# MFX.net
KiCad netlist of a schematic drawn in Altium Designer
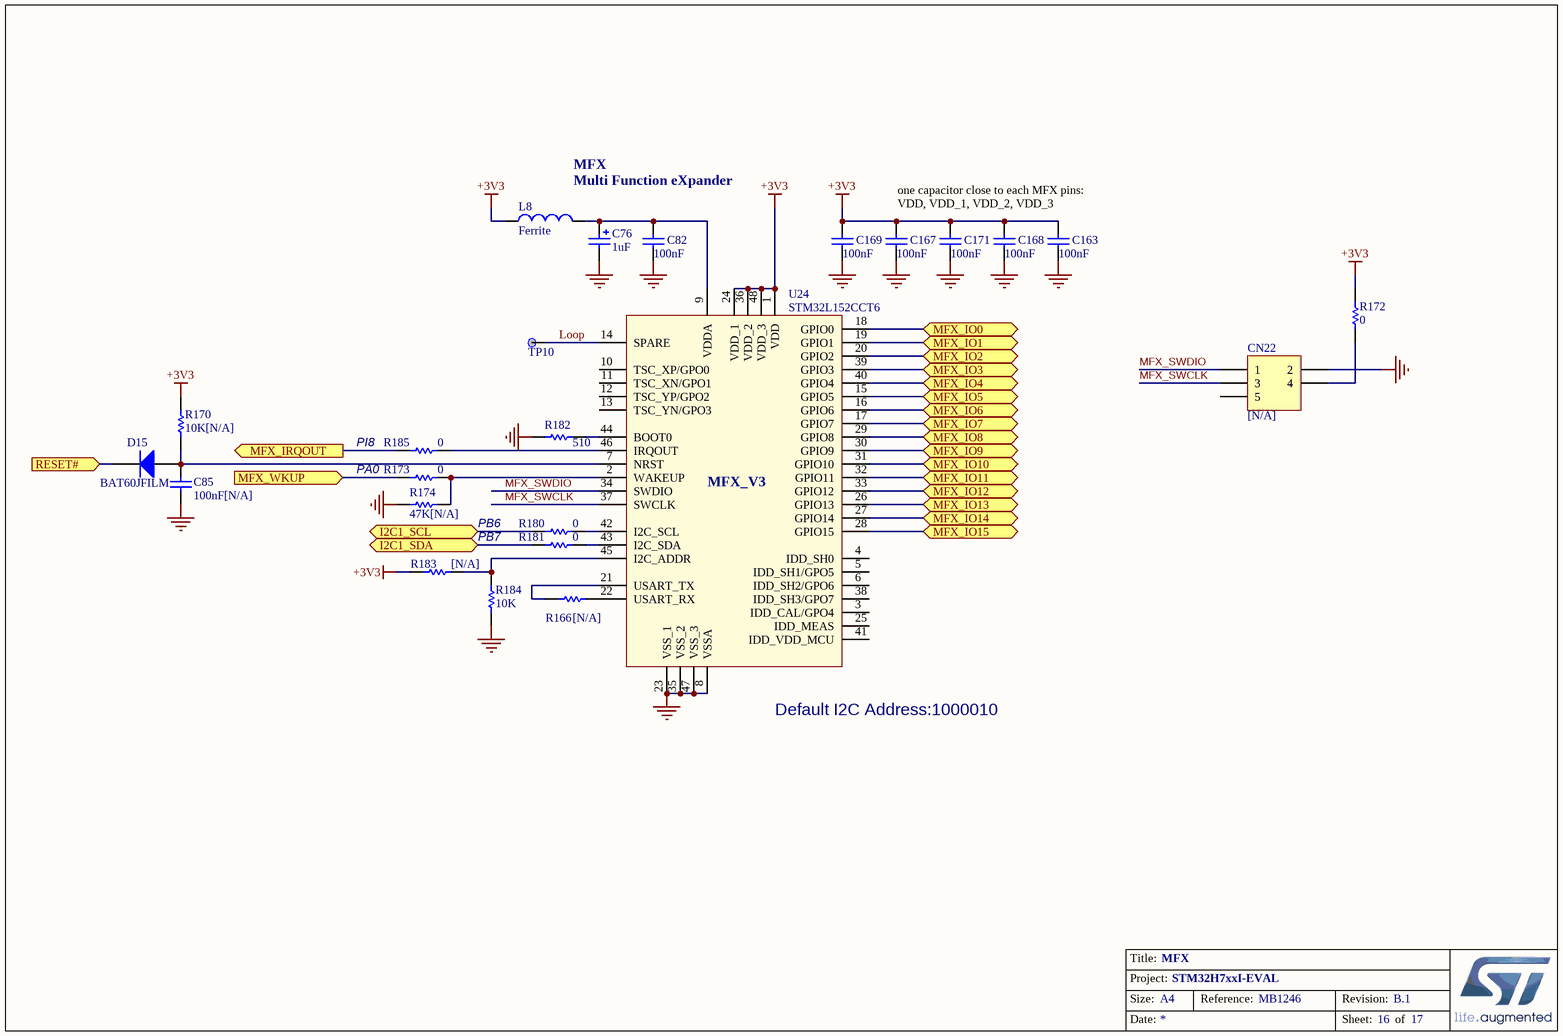
[diagram p0: MFX.SchDoc]

(export (version "E")
  (design (tool "Eeschema 10.0.6"))
  (components
    (comp (ref "C76")
      (value "1uF")
      (footprint "TAN-A")
      (description "Polarized Capacitor,1uF,16V,10%,typeA,AVX")
      (libsource (lib "MCD_TOOLS") (part "Cap_1uF_POL_10%_TANA"))
    )
    (comp (ref "C82")
      (value "100nF")
      (footprint "0402C")
      (description "Capacitor,100nF,16V,X7R,10%,0402,YAGEO")
      (libsource (lib "MCD_TOOLS") (part "Cap_100nF_X7R_10%_0402"))
    )
    (comp (ref "C85")
      (value "100nF[N/A]")
      (footprint "0402C")
      (description "Capacitor,100nF,16V,X7R,10%,0402,YAGEO")
      (libsource (lib "MCD_TOOLS") (part "Cap_100nF_X7R_10%_0402"))
    )
    (comp (ref "C163")
      (value "100nF")
      (footprint "0402C")
      (description "Capacitor,100nF,16V,X7R,10%,0402,YAGEO")
      (libsource (lib "MCD_TOOLS") (part "Cap_100nF_X7R_10%_0402"))
    )
    (comp (ref "C167")
      (value "100nF")
      (footprint "0402C")
      (description "Capacitor,100nF,16V,X7R,10%,0402,YAGEO")
      (libsource (lib "MCD_TOOLS") (part "Cap_100nF_X7R_10%_0402"))
    )
    (comp (ref "C168")
      (value "100nF")
      (footprint "0402C")
      (description "Capacitor,100nF,16V,X7R,10%,0402,YAGEO")
      (libsource (lib "MCD_TOOLS") (part "Cap_100nF_X7R_10%_0402"))
    )
    (comp (ref "C169")
      (value "100nF")
      (footprint "0402C")
      (description "Capacitor,100nF,16V,X7R,10%,0402,YAGEO")
      (libsource (lib "MCD_TOOLS") (part "Cap_100nF_X7R_10%_0402"))
    )
    (comp (ref "C171")
      (value "100nF")
      (footprint "0402C")
      (description "Capacitor,100nF,16V,X7R,10%,0402,YAGEO")
      (libsource (lib "MCD_TOOLS") (part "Cap_100nF_X7R_10%_0402"))
    )
    (comp (ref "CN22")
      (value "[N/A]")
      (footprint "HDR_2X3-1_2R54-6")
      (description "Header, 3-Pin, Dual row")
      (fields (field (name "PUBLISHER") "Altium Limited"))
      (libsource (lib "Miscellaneous Connectors") (part "Header 3X2"))
    )
    (comp (ref "D15")
      (value "BAT60JFILM")
      (footprint "SOD-323")
      (description "Default Diode")
      (fields (field (name "PUBLISHER") "Altium Limited"))
      (libsource (lib "Miscellaneous Devices") (part "Diode"))
    )
    (comp (ref "L8")
      (value "Ferrite")
      (footprint "0603L")
      (description "Bead,600R,350mA,0603,FCM1608KF-601T03,Tai-tech")
      (libsource (lib "MCD_TOOLS") (part "BEAD_600R_350MA_0603"))
    )
    (comp (ref "R166")
      (value "[N/A]")
      (footprint "0603R")
      (description "Resistor")
      (fields (field (name "PUBLISHER") "Altium Limited"))
      (libsource (lib "Miscellaneous Devices") (part "res1"))
    )
    (comp (ref "R170")
      (value "10K[N/A]")
      (footprint "0402R")
      (description "Resistor 0402 or 0603 or 0805")
      (libsource (lib "MCD_TOOLS") (part "Resistor_ST"))
    )
    (comp (ref "R172")
      (value "0")
      (footprint "0603R")
      (description "Resistor")
      (fields (field (name "PUBLISHER") "Altium Limited"))
      (libsource (lib "Miscellaneous Devices") (part "Res1"))
    )
    (comp (ref "R173")
      (value "0")
      (footprint "0603R")
      (description "Resistor")
      (fields (field (name "PUBLISHER") "Altium Limited"))
      (libsource (lib "Miscellaneous Devices") (part "Res1"))
    )
    (comp (ref "R174")
      (value "47K[N/A]")
      (footprint "0402R")
      (description "Resistor 0402 or 0603 or 0805")
      (libsource (lib "MCD_TOOLS") (part "Resistor_ST"))
    )
    (comp (ref "R180")
      (value "0")
      (footprint "0603R")
      (description "Resistor")
      (fields (field (name "PUBLISHER") "Altium Limited"))
      (libsource (lib "Miscellaneous Devices") (part "Res1"))
    )
    (comp (ref "R181")
      (value "0")
      (footprint "0603R")
      (description "Resistor")
      (fields (field (name "PUBLISHER") "Altium Limited"))
      (libsource (lib "Miscellaneous Devices") (part "Res1"))
    )
    (comp (ref "R182")
      (value "510")
      (footprint "0402R")
      (description "Resistor 0402 or 0603 or 0805")
      (libsource (lib "MCD_TOOLS") (part "Resistor_ST"))
    )
    (comp (ref "R183")
      (value "[N/A]")
      (footprint "0603R")
      (description "Resistor")
      (fields (field (name "PUBLISHER") "Altium Limited"))
      (libsource (lib "Miscellaneous Devices") (part "Res1"))
    )
    (comp (ref "R184")
      (value "10K")
      (footprint "0402R")
      (description "Resistor 0402 or 0603 or 0805")
      (libsource (lib "MCD_TOOLS") (part "Resistor_ST"))
    )
    (comp (ref "R185")
      (value "0")
      (footprint "0603R")
      (description "Resistor")
      (fields (field (name "PUBLISHER") "Altium Limited"))
      (libsource (lib "Miscellaneous Devices") (part "Res1"))
    )
    (comp (ref "TP10") (value "~") (footprint "TP") (libsource (lib "*") (part "TP")))
    (comp (ref "U24")
      (value "STM32L152CCT6")
      (footprint "LQFP48_0R5_9X9")
      (description "Multifunction expander")
      (libsource (lib "MB1167") (part "MFX"))
    )
  )
  (nets
    (net (code "1") (name "+3V3") (class "Default")
      (node (ref "C163") (pin "2") (pinfunction "2_2") (pintype "passive"))
      (node (ref "C167") (pin "2") (pinfunction "2_2") (pintype "passive"))
      (node (ref "C168") (pin "2") (pinfunction "2_2") (pintype "passive"))
      (node (ref "C169") (pin "2") (pinfunction "2_2") (pintype "passive"))
      (node (ref "C171") (pin "1") (pinfunction "1_1") (pintype "passive"))
      (node (ref "L8") (pin "1") (pinfunction "1_1") (pintype "passive"))
      (node (ref "R170") (pin "2") (pinfunction "2_2") (pintype "passive"))
      (node (ref "R172") (pin "1") (pinfunction "1_1") (pintype "passive"))
      (node (ref "R183") (pin "2") (pinfunction "2_2") (pintype "passive"))
      (node (ref "U24") (pin "1") (pinfunction "VDD_1") (pintype "passive"))
      (node (ref "U24") (pin "24") (pinfunction "VDD_1_24") (pintype "passive"))
      (node (ref "U24") (pin "36") (pinfunction "VDD_2_36") (pintype "passive"))
      (node (ref "U24") (pin "48") (pinfunction "VDD_3_48") (pintype "passive"))
    )
    (net (code "2") (name "/I2C1_SCL") (class "Default")
      (node (ref "R180") (pin "1") (pinfunction "1_1") (pintype "passive"))
    )
    (net (code "3") (name "/I2C1_SDA") (class "Default")
      (node (ref "R181") (pin "1") (pinfunction "1_1") (pintype "passive"))
    )
    (net (code "4") (name "/Loop") (class "Default")
      (node (ref "TP10") (pin "1") (pinfunction "1_1") (pintype "passive"))
      (node (ref "U24") (pin "14") (pinfunction "SPARE_14") (pintype "passive"))
    )
    (net (code "5") (name "/MFX_IO0") (class "Default")
      (node (ref "U24") (pin "18") (pinfunction "GPIO0_18") (pintype "passive"))
    )
    (net (code "6") (name "/MFX_IO1") (class "Default")
      (node (ref "U24") (pin "19") (pinfunction "GPIO1_19") (pintype "passive"))
    )
    (net (code "7") (name "/MFX_IO2") (class "Default")
      (node (ref "U24") (pin "20") (pinfunction "GPIO2_20") (pintype "passive"))
    )
    (net (code "8") (name "/MFX_IO3") (class "Default")
      (node (ref "U24") (pin "39") (pinfunction "GPIO3_39") (pintype "passive"))
    )
    (net (code "9") (name "/MFX_IO4") (class "Default")
      (node (ref "U24") (pin "40") (pinfunction "GPIO4_40") (pintype "passive"))
    )
    (net (code "10") (name "/MFX_IO5") (class "Default")
      (node (ref "U24") (pin "15") (pinfunction "GPIO5_15") (pintype "passive"))
    )
    (net (code "11") (name "/MFX_IO6") (class "Default")
      (node (ref "U24") (pin "16") (pinfunction "GPIO6_16") (pintype "passive"))
    )
    (net (code "12") (name "/MFX_IO7") (class "Default")
      (node (ref "U24") (pin "17") (pinfunction "GPIO7_17") (pintype "passive"))
    )
    (net (code "13") (name "/MFX_IO8") (class "Default")
      (node (ref "U24") (pin "29") (pinfunction "GPIO8_29") (pintype "passive"))
    )
    (net (code "14") (name "/MFX_IO9") (class "Default")
      (node (ref "U24") (pin "30") (pinfunction "GPIO9_30") (pintype "passive"))
    )
    (net (code "15") (name "/MFX_IO10") (class "Default")
      (node (ref "U24") (pin "31") (pinfunction "GPIO10_31") (pintype "passive"))
    )
    (net (code "16") (name "/MFX_IO11") (class "Default")
      (node (ref "U24") (pin "32") (pinfunction "GPIO11_32") (pintype "passive"))
    )
    (net (code "17") (name "/MFX_IO12") (class "Default")
      (node (ref "U24") (pin "33") (pinfunction "GPIO12_33") (pintype "passive"))
    )
    (net (code "18") (name "/MFX_IO13") (class "Default")
      (node (ref "U24") (pin "26") (pinfunction "GPIO13_26") (pintype "passive"))
    )
    (net (code "19") (name "/MFX_IO14") (class "Default")
      (node (ref "U24") (pin "27") (pinfunction "GPIO14_27") (pintype "passive"))
    )
    (net (code "20") (name "/MFX_IO15") (class "Default")
      (node (ref "U24") (pin "28") (pinfunction "GPIO15_28") (pintype "passive"))
    )
    (net (code "21") (name "/MFX_IRQOUT") (class "Default")
      (node (ref "R185") (pin "1") (pinfunction "1_1") (pintype "passive"))
    )
    (net (code "22") (name "/MFX_SWCLK") (class "Default")
      (node (ref "CN22") (pin "3") (pinfunction "3_3") (pintype "passive"))
      (node (ref "U24") (pin "37") (pinfunction "SWCLK_37") (pintype "passive"))
    )
    (net (code "23") (name "/MFX_SWDIO") (class "Default")
      (node (ref "CN22") (pin "1") (pinfunction "1_1") (pintype "passive"))
      (node (ref "U24") (pin "34") (pinfunction "SWDIO_34") (pintype "passive"))
    )
    (net (code "24") (name "/MFX_WKUP") (class "Default")
      (node (ref "R173") (pin "2") (pinfunction "2_2") (pintype "passive"))
    )
    (net (code "25") (name "/RESET#") (class "Default")
      (node (ref "D15") (pin "2") (pinfunction "K_2") (pintype "passive"))
    )
    (net (code "26") (name "GND") (class "Default")
      (node (ref "C163") (pin "1") (pinfunction "1_1") (pintype "passive"))
      (node (ref "C167") (pin "1") (pinfunction "1_1") (pintype "passive"))
      (node (ref "C168") (pin "1") (pinfunction "1_1") (pintype "passive"))
      (node (ref "C169") (pin "1") (pinfunction "1_1") (pintype "passive"))
      (node (ref "C171") (pin "2") (pinfunction "2_2") (pintype "passive"))
      (node (ref "C76") (pin "2") (pinfunction "2_2") (pintype "passive"))
      (node (ref "C82") (pin "1") (pinfunction "1_1") (pintype "passive"))
      (node (ref "C85") (pin "1") (pinfunction "1_1") (pintype "passive"))
      (node (ref "CN22") (pin "2") (pinfunction "2_2") (pintype "passive"))
      (node (ref "R174") (pin "1") (pinfunction "1_1") (pintype "passive"))
      (node (ref "R182") (pin "2") (pinfunction "2_2") (pintype "passive"))
      (node (ref "R184") (pin "2") (pinfunction "2_2") (pintype "passive"))
      (node (ref "U24") (pin "23") (pinfunction "VSS_1_23") (pintype "passive"))
      (node (ref "U24") (pin "35") (pinfunction "VSS_2_35") (pintype "passive"))
      (node (ref "U24") (pin "47") (pinfunction "VSS_3_47") (pintype "passive"))
      (node (ref "U24") (pin "8") (pinfunction "VSSA_8") (pintype "passive"))
    )
    (net (code "27") (name "Net-(CN22-Pad4)") (class "Default")
      (node (ref "CN22") (pin "4") (pinfunction "4_4") (pintype "passive"))
      (node (ref "R172") (pin "2") (pinfunction "2_2") (pintype "passive"))
    )
    (net (code "28") (name "Net-(D15-A)") (class "Default")
      (node (ref "C85") (pin "2") (pinfunction "2_2") (pintype "passive"))
      (node (ref "D15") (pin "1") (pinfunction "A_1") (pintype "passive"))
      (node (ref "R170") (pin "1") (pinfunction "1_1") (pintype "passive"))
      (node (ref "U24") (pin "7") (pinfunction "NRST_7") (pintype "passive"))
    )
    (net (code "29") (name "Net-(U24-BOOT0)") (class "Default")
      (node (ref "R182") (pin "1") (pinfunction "1_1") (pintype "passive"))
      (node (ref "U24") (pin "44") (pinfunction "BOOT0_44") (pintype "passive"))
    )
    (net (code "30") (name "Net-(U24-I2C_ADDR)") (class "Default")
      (node (ref "R183") (pin "1") (pinfunction "1_1") (pintype "passive"))
      (node (ref "R184") (pin "1") (pinfunction "1_1") (pintype "passive"))
      (node (ref "U24") (pin "45") (pinfunction "I2C_ADDR_45") (pintype "passive"))
    )
    (net (code "31") (name "Net-(U24-I2C_SCL)") (class "Default")
      (node (ref "R180") (pin "2") (pinfunction "2_2") (pintype "passive"))
      (node (ref "U24") (pin "42") (pinfunction "I2C_SCL_42") (pintype "passive"))
    )
    (net (code "32") (name "Net-(U24-I2C_SDA)") (class "Default")
      (node (ref "R181") (pin "2") (pinfunction "2_2") (pintype "passive"))
      (node (ref "U24") (pin "43") (pinfunction "I2C_SDA_43") (pintype "passive"))
    )
    (net (code "33") (name "Net-(U24-IRQOUT)") (class "Default")
      (node (ref "R185") (pin "2") (pinfunction "2_2") (pintype "passive"))
      (node (ref "U24") (pin "46") (pinfunction "IRQOUT_46") (pintype "passive"))
    )
    (net (code "34") (name "Net-(U24-USART_RX)") (class "Default")
      (node (ref "R166") (pin "2") (pinfunction "2_2") (pintype "passive"))
      (node (ref "U24") (pin "22") (pinfunction "USART_RX_22") (pintype "passive"))
    )
    (net (code "35") (name "Net-(U24-USART_TX)") (class "Default")
      (node (ref "R166") (pin "1") (pinfunction "1_1") (pintype "passive"))
      (node (ref "U24") (pin "21") (pinfunction "USART_TX_21") (pintype "passive"))
    )
    (net (code "36") (name "Net-(U24-VDDA)") (class "Default")
      (node (ref "C76") (pin "1") (pinfunction "1_1") (pintype "passive"))
      (node (ref "C82") (pin "2") (pinfunction "2_2") (pintype "passive"))
      (node (ref "L8") (pin "2") (pinfunction "2_2") (pintype "passive"))
      (node (ref "U24") (pin "9") (pinfunction "VDDA_9") (pintype "passive"))
    )
    (net (code "37") (name "Net-(U24-WAKEUP)") (class "Default")
      (node (ref "R173") (pin "1") (pinfunction "1_1") (pintype "passive"))
      (node (ref "R174") (pin "2") (pinfunction "2_2") (pintype "passive"))
      (node (ref "U24") (pin "2") (pinfunction "WAKEUP_2") (pintype "passive"))
    )
    (net (code "38") (name "unconnected-(CN22-Pad5)") (class "Default")
      (node (ref "CN22") (pin "5") (pinfunction "5_5") (pintype "passive"))
    )
    (net (code "39") (name "unconnected-(U24-IDD_CAL{slash}GPO4-Pad3)") (class "Default")
      (node (ref "U24") (pin "3") (pinfunction "IDD_CAL/GPO4_3") (pintype "passive"))
    )
    (net (code "40") (name "unconnected-(U24-IDD_MEAS-Pad25)") (class "Default")
      (node (ref "U24") (pin "25") (pinfunction "IDD_MEAS_25") (pintype "passive"))
    )
    (net (code "41") (name "unconnected-(U24-IDD_SH0-Pad4)") (class "Default")
      (node (ref "U24") (pin "4") (pinfunction "IDD_SH0_4") (pintype "passive"))
    )
    (net (code "42") (name "unconnected-(U24-IDD_SH1{slash}GPO5-Pad5)") (class "Default")
      (node (ref "U24") (pin "5") (pinfunction "IDD_SH1/GPO5_5") (pintype "passive"))
    )
    (net (code "43") (name "unconnected-(U24-IDD_SH2{slash}GPO6-Pad6)") (class "Default")
      (node (ref "U24") (pin "6") (pinfunction "IDD_SH2/GPO6_6") (pintype "passive"))
    )
    (net (code "44") (name "unconnected-(U24-IDD_SH3{slash}GPO7-Pad38)") (class "Default")
      (node (ref "U24") (pin "38") (pinfunction "IDD_SH3/GPO7_38") (pintype "passive"))
    )
    (net (code "45") (name "unconnected-(U24-IDD_VDD_MCU-Pad41)") (class "Default")
      (node (ref "U24") (pin "41") (pinfunction "IDD_VDD_MCU_41") (pintype "passive"))
    )
    (net (code "46") (name "unconnected-(U24-TSC_XN{slash}GPO1-Pad11)") (class "Default")
      (node (ref "U24") (pin "11") (pinfunction "TSC_XN/GPO1_11") (pintype "passive"))
    )
    (net (code "47") (name "unconnected-(U24-TSC_XP{slash}GPO0-Pad10)") (class "Default")
      (node (ref "U24") (pin "10") (pinfunction "TSC_XP/GPO0_10") (pintype "passive"))
    )
    (net (code "48") (name "unconnected-(U24-TSC_YN{slash}GPO3-Pad13)") (class "Default")
      (node (ref "U24") (pin "13") (pinfunction "TSC_YN/GPO3_13") (pintype "passive"))
    )
    (net (code "49") (name "unconnected-(U24-TSC_YP{slash}GPO2-Pad12)") (class "Default")
      (node (ref "U24") (pin "12") (pinfunction "TSC_YP/GPO2_12") (pintype "passive"))
    )
  )
)
